# Sheet1.net
KiCad netlist of a schematic drawn in Altium Designer
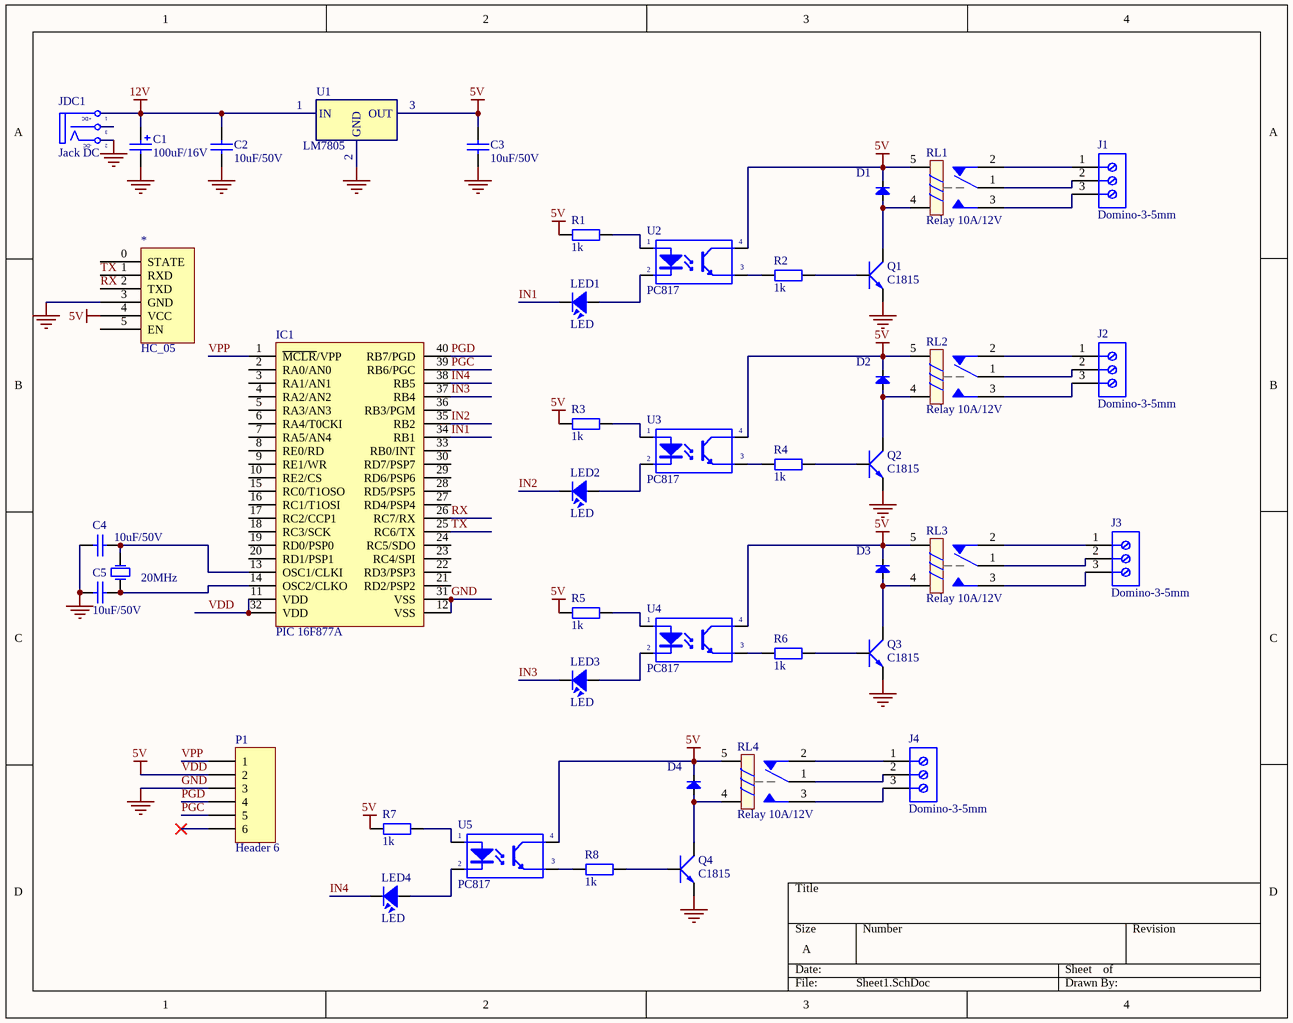
[diagram p0: Sheet1.SchDoc]

(export (version "E")
  (design (tool "Eeschema 10.0.6"))
  (components
    (comp (ref "*") (value "HC_05") (footprint "HC_05") (libsource (lib "C_20_addition") (part "HC_05")))
    (comp (ref "C1")
      (value "100uF/16V")
      (footprint "CAP-SM-AL-SIZE-D-D6L6")
      (description "CAP ALUM 100UF 20% 16V SMD")
      (fields
        (field (name "MANUFACTURER") "Nichicon")
        (field (name "MANUFACTURER PART NUMBER") "UWX1C101MCL1GB")
      )
      (libsource (lib "Capacitor") (part "Cap-Al-100uF-16V-D6L5"))
    )
    (comp (ref "C2")
      (value "10uF/50V")
      (footprint "CAP-SM-0805")
      (description "CAP CER 10UF 50V X5R 0805")
      (fields
        (field (name "MANUFACTURER") "Yageo")
        (field (name "MANUFACTURER PART NUMBER") "CC0805KKX5R9BB106")
      )
      (libsource (lib "Capacitor") (part "Cap-10uF-50V-0805"))
    )
    (comp (ref "C3")
      (value "10uF/50V")
      (footprint "CAP-SM-0805")
      (description "CAP CER 10UF 50V X5R 0805")
      (fields
        (field (name "MANUFACTURER") "Yageo")
        (field (name "MANUFACTURER PART NUMBER") "CC0805KKX5R9BB106")
      )
      (libsource (lib "Capacitor") (part "Cap-10uF-50V-0805"))
    )
    (comp (ref "C4")
      (value "10uF/50V")
      (footprint "CAP-SM-0805")
      (description "CAP CER 10UF 50V X5R 0805")
      (fields
        (field (name "MANUFACTURER") "Yageo")
        (field (name "MANUFACTURER PART NUMBER") "CC0805KKX5R9BB106")
      )
      (libsource (lib "Capacitor") (part "Cap-10uF-50V-0805"))
    )
    (comp (ref "C5")
      (value "10uF/50V")
      (footprint "CAP-SM-0805")
      (description "CAP CER 10UF 50V X5R 0805")
      (fields
        (field (name "MANUFACTURER") "Yageo")
        (field (name "MANUFACTURER PART NUMBER") "CC0805KKX5R9BB106")
      )
      (libsource (lib "Capacitor") (part "Cap-10uF-50V-0805"))
    )
    (comp (ref "D1")
      (value "Diode")
      (footprint "DIO-1A")
      (description "Default Diode")
      (fields (field (name "PUBLISHER") "Altium Limited"))
      (libsource (lib "My Library") (part "Diode"))
    )
    (comp (ref "D2")
      (value "Diode")
      (footprint "DIO-1A")
      (description "Default Diode")
      (fields (field (name "PUBLISHER") "Altium Limited"))
      (libsource (lib "My Library") (part "Diode"))
    )
    (comp (ref "D3")
      (value "Diode")
      (footprint "DIO-1A")
      (description "Default Diode")
      (fields (field (name "PUBLISHER") "Altium Limited"))
      (libsource (lib "My Library") (part "Diode"))
    )
    (comp (ref "D4")
      (value "Diode")
      (footprint "DIO-1A")
      (description "Default Diode")
      (fields (field (name "PUBLISHER") "Altium Limited"))
      (libsource (lib "My Library") (part "Diode"))
    )
    (comp (ref "IC1")
      (value "PIC 16F877A")
      (footprint "DIP40/W0.6")
      (description "8K FLASH, 368B RAM, 256B EFROM")
      (fields (field (name "COPYRIGHT BY") "VanDungEvn"))
      (libsource (lib "My Library") (part "PIC16F877-PU"))
    )
    (comp (ref "J1")
      (value "Domino-3-5mm")
      (footprint "DOMINO-3-5mm")
      (description "WR-TBL Serie 1347 Horizontal Cable Entry, Pressure Clamp, pitch 5mm, 3p")
      (fields (field (name "PART NUMBER") "691134710003") (field (name "PUBLISHER") "Wurth Elektronik"))
      (libsource (lib "Header-connector") (part "Domino-3-5mm"))
    )
    (comp (ref "J2")
      (value "Domino-3-5mm")
      (footprint "DOMINO-3-5mm")
      (description "WR-TBL Serie 1347 Horizontal Cable Entry, Pressure Clamp, pitch 5mm, 3p")
      (fields (field (name "PART NUMBER") "691134710003") (field (name "PUBLISHER") "Wurth Elektronik"))
      (libsource (lib "Header-connector") (part "Domino-3-5mm"))
    )
    (comp (ref "J3")
      (value "Domino-3-5mm")
      (footprint "DOMINO-3-5mm")
      (description "WR-TBL Serie 1347 Horizontal Cable Entry, Pressure Clamp, pitch 5mm, 3p")
      (fields (field (name "PART NUMBER") "691134710003") (field (name "PUBLISHER") "Wurth Elektronik"))
      (libsource (lib "Header-connector") (part "Domino-3-5mm"))
    )
    (comp (ref "J4")
      (value "Domino-3-5mm")
      (footprint "DOMINO-3-5mm")
      (description "WR-TBL Serie 1347 Horizontal Cable Entry, Pressure Clamp, pitch 5mm, 3p")
      (fields (field (name "PART NUMBER") "691134710003") (field (name "PUBLISHER") "Wurth Elektronik"))
      (libsource (lib "Header-connector") (part "Domino-3-5mm"))
    )
    (comp (ref "JDC1")
      (value "Jack DC")
      (footprint "JACK-DC")
      (description "Jack DC input")
      (libsource (lib "Header-connector") (part "Jack DC"))
    )
    (comp (ref "LED1")
      (value "LED")
      (footprint "LED-3")
      (description "LED Single colour Green and Red")
      (libsource (lib "syhaunguyen") (part "LED"))
    )
    (comp (ref "LED2")
      (value "LED")
      (footprint "LED-3")
      (description "LED Single colour Green and Red")
      (libsource (lib "syhaunguyen") (part "LED"))
    )
    (comp (ref "LED3")
      (value "LED")
      (footprint "LED-3")
      (description "LED Single colour Green and Red")
      (libsource (lib "syhaunguyen") (part "LED"))
    )
    (comp (ref "LED4")
      (value "LED")
      (footprint "LED-3")
      (description "LED Single colour Green and Red")
      (libsource (lib "syhaunguyen") (part "LED"))
    )
    (comp (ref "P1")
      (value "Header 6")
      (footprint "HDR1X6")
      (description "Header, 6-Pin")
      (fields (field (name "PUBLISHER") "Altium Limited"))
      (libsource (lib "My Library") (part "Header 6"))
    )
    (comp (ref "Q1")
      (value "C1815")
      (footprint "QTO-92")
      (description "NPN 600mW, ECB")
      (libsource (lib "syhaunguyen") (part "C1815"))
    )
    (comp (ref "Q2")
      (value "C1815")
      (footprint "QTO-92")
      (description "NPN 600mW, ECB")
      (libsource (lib "syhaunguyen") (part "C1815"))
    )
    (comp (ref "Q3")
      (value "C1815")
      (footprint "QTO-92")
      (description "NPN 600mW, ECB")
      (libsource (lib "syhaunguyen") (part "C1815"))
    )
    (comp (ref "Q4")
      (value "C1815")
      (footprint "QTO-92")
      (description "NPN 600mW, ECB")
      (libsource (lib "syhaunguyen") (part "C1815"))
    )
    (comp (ref "R1")
      (value "1k")
      (footprint "R1/4W")
      (description "Resistor 1/4W")
      (libsource (lib "My Library") (part "R1/4W"))
    )
    (comp (ref "R2")
      (value "1k")
      (footprint "R1/4W")
      (description "Resistor 1/4W")
      (libsource (lib "My Library") (part "R1/4W"))
    )
    (comp (ref "R3")
      (value "1k")
      (footprint "R1/4W")
      (description "Resistor 1/4W")
      (libsource (lib "My Library") (part "R1/4W"))
    )
    (comp (ref "R4")
      (value "1k")
      (footprint "R1/4W")
      (description "Resistor 1/4W")
      (libsource (lib "My Library") (part "R1/4W"))
    )
    (comp (ref "R5")
      (value "1k")
      (footprint "R1/4W")
      (description "Resistor 1/4W")
      (libsource (lib "My Library") (part "R1/4W"))
    )
    (comp (ref "R6")
      (value "1k")
      (footprint "R1/4W")
      (description "Resistor 1/4W")
      (libsource (lib "My Library") (part "R1/4W"))
    )
    (comp (ref "R7")
      (value "1k")
      (footprint "R1/4W")
      (description "Resistor 1/4W")
      (libsource (lib "My Library") (part "R1/4W"))
    )
    (comp (ref "R8")
      (value "1k")
      (footprint "R1/4W")
      (description "Resistor 1/4W")
      (libsource (lib "My Library") (part "R1/4W"))
    )
    (comp (ref "RL1")
      (value "Relay 10A/12V")
      (footprint "RL_SPDT_10A")
      (description "Relay SPDT,10A - 12VDC 5 Pin")
      (libsource (lib "My Library") (part "Relay 1"))
    )
    (comp (ref "RL2")
      (value "Relay 10A/12V")
      (footprint "RL_SPDT_10A")
      (description "Relay SPDT,10A - 12VDC 5 Pin")
      (libsource (lib "My Library") (part "Relay 1"))
    )
    (comp (ref "RL3")
      (value "Relay 10A/12V")
      (footprint "RL_SPDT_10A")
      (description "Relay SPDT,10A - 12VDC 5 Pin")
      (libsource (lib "My Library") (part "Relay 1"))
    )
    (comp (ref "RL4")
      (value "Relay 10A/12V")
      (footprint "RL_SPDT_10A")
      (description "Relay SPDT,10A - 12VDC 5 Pin")
      (libsource (lib "My Library") (part "Relay 1"))
    )
    (comp (ref "U1")
      (value "LM7805")
      (footprint "QTO-220")
      (description "Positive Voltage Regulator")
      (libsource (lib "PIF_C16_2_lib") (part "LM7805"))
    )
    (comp (ref "U2")
      (value "PC817")
      (footprint "DIP4/W0.3")
      (description "Single Opto")
      (libsource (lib "syhaunguyen") (part "PC817"))
    )
    (comp (ref "U3")
      (value "PC817")
      (footprint "DIP4/W0.3")
      (description "Single Opto")
      (libsource (lib "syhaunguyen") (part "PC817"))
    )
    (comp (ref "U4")
      (value "PC817")
      (footprint "DIP4/W0.3")
      (description "Single Opto")
      (libsource (lib "syhaunguyen") (part "PC817"))
    )
    (comp (ref "U5")
      (value "PC817")
      (footprint "DIP4/W0.3")
      (description "Single Opto")
      (libsource (lib "syhaunguyen") (part "PC817"))
    )
    (comp (ref "Y1")
      (value "20MHz")
      (footprint "XTAL")
      (description "Crystal Oscillator")
      (fields (field (name "PUBLISHER") "Altium Limited"))
      (libsource (lib "My Library") (part "XTAL"))
    )
  )
  (nets
    (net (code "1") (name "/IN1") (class "Default")
      (node (ref "IC1") (pin "34") (pinfunction "RB1_34") (pintype "passive"))
      (node (ref "LED1") (pin "2") (pinfunction "2_2") (pintype "passive"))
    )
    (net (code "2") (name "/IN2") (class "Default")
      (node (ref "IC1") (pin "35") (pinfunction "RB2_35") (pintype "passive"))
      (node (ref "LED2") (pin "2") (pinfunction "2_2") (pintype "passive"))
    )
    (net (code "3") (name "/IN3") (class "Default")
      (node (ref "IC1") (pin "37") (pinfunction "RB4_37") (pintype "passive"))
      (node (ref "LED3") (pin "2") (pinfunction "2_2") (pintype "passive"))
    )
    (net (code "4") (name "/IN4") (class "Default")
      (node (ref "IC1") (pin "38") (pinfunction "RB5_38") (pintype "passive"))
      (node (ref "LED4") (pin "2") (pinfunction "2_2") (pintype "passive"))
    )
    (net (code "5") (name "/PGC") (class "Default")
      (node (ref "IC1") (pin "39") (pinfunction "RB6/PGC_39") (pintype "passive"))
      (node (ref "P1") (pin "5") (pinfunction "5_5") (pintype "passive"))
    )
    (net (code "6") (name "/PGD") (class "Default")
      (node (ref "IC1") (pin "40") (pinfunction "RB7/PGD_40") (pintype "passive"))
      (node (ref "P1") (pin "4") (pinfunction "4_4") (pintype "passive"))
    )
    (net (code "7") (name "/RX") (class "Default")
      (node (ref "*") (pin "2") (pinfunction "TXD_2") (pintype "passive"))
      (node (ref "IC1") (pin "26") (pinfunction "RC7/RX_26") (pintype "passive"))
    )
    (net (code "8") (name "/TX") (class "Default")
      (node (ref "*") (pin "1") (pinfunction "RXD_1") (pintype "passive"))
      (node (ref "IC1") (pin "25") (pinfunction "RC6/TX_25") (pintype "passive"))
    )
    (net (code "9") (name "/VPP") (class "Default")
      (node (ref "IC1") (pin "1") (pinfunction "~{MCLR}/VPP_1") (pintype "passive"))
      (node (ref "P1") (pin "1") (pinfunction "1_1") (pintype "passive"))
    )
    (net (code "10") (name "5V") (class "Default")
      (node (ref "*") (pin "4") (pinfunction "VCC_4") (pintype "passive"))
      (node (ref "C3") (pin "2") (pinfunction "2_2") (pintype "passive"))
      (node (ref "D1") (pin "2") (pinfunction "K_2") (pintype "passive"))
      (node (ref "D2") (pin "2") (pinfunction "K_2") (pintype "passive"))
      (node (ref "D3") (pin "2") (pinfunction "K_2") (pintype "passive"))
      (node (ref "D4") (pin "2") (pinfunction "K_2") (pintype "passive"))
      (node (ref "IC1") (pin "11") (pinfunction "VDD_11") (pintype "passive"))
      (node (ref "IC1") (pin "32") (pinfunction "VDD_32") (pintype "passive"))
      (node (ref "P1") (pin "2") (pinfunction "2_2") (pintype "passive"))
      (node (ref "R1") (pin "1") (pinfunction "1_1") (pintype "passive"))
      (node (ref "R3") (pin "1") (pinfunction "1_1") (pintype "passive"))
      (node (ref "R5") (pin "1") (pinfunction "1_1") (pintype "passive"))
      (node (ref "R7") (pin "1") (pinfunction "1_1") (pintype "passive"))
      (node (ref "RL1") (pin "5") (pinfunction "5_5") (pintype "passive"))
      (node (ref "RL2") (pin "5") (pinfunction "5_5") (pintype "passive"))
      (node (ref "RL3") (pin "5") (pinfunction "5_5") (pintype "passive"))
      (node (ref "RL4") (pin "5") (pinfunction "5_5") (pintype "passive"))
      (node (ref "U1") (pin "3") (pinfunction "OUT_3") (pintype "power_in"))
      (node (ref "U2") (pin "4") (pinfunction "C_4") (pintype "passive"))
      (node (ref "U3") (pin "4") (pinfunction "C_4") (pintype "passive"))
      (node (ref "U4") (pin "4") (pinfunction "C_4") (pintype "passive"))
      (node (ref "U5") (pin "4") (pinfunction "C_4") (pintype "passive"))
    )
    (net (code "11") (name "12V") (class "Default")
      (node (ref "C1") (pin "1") (pinfunction "1_1") (pintype "passive"))
      (node (ref "C2") (pin "2") (pinfunction "2_2") (pintype "passive"))
      (node (ref "JDC1") (pin "1") (pinfunction "T_1") (pintype "passive"))
      (node (ref "U1") (pin "1") (pinfunction "IN_1") (pintype "power_in"))
    )
    (net (code "12") (name "GND") (class "Default")
      (node (ref "*") (pin "3") (pinfunction "GND_3") (pintype "passive"))
      (node (ref "C1") (pin "2") (pinfunction "2_2") (pintype "passive"))
      (node (ref "C2") (pin "1") (pinfunction "1_1") (pintype "passive"))
      (node (ref "C3") (pin "1") (pinfunction "1_1") (pintype "passive"))
      (node (ref "C4") (pin "2") (pinfunction "2_2") (pintype "passive"))
      (node (ref "C5") (pin "2") (pinfunction "2_2") (pintype "passive"))
      (node (ref "IC1") (pin "12") (pinfunction "VSS_12") (pintype "passive"))
      (node (ref "IC1") (pin "31") (pinfunction "VSS_31") (pintype "passive"))
      (node (ref "JDC1") (pin "2") (pinfunction "TN_2") (pintype "passive"))
      (node (ref "P1") (pin "3") (pinfunction "3_3") (pintype "passive"))
      (node (ref "Q1") (pin "1") (pinfunction "E_1") (pintype "passive"))
      (node (ref "Q2") (pin "1") (pinfunction "E_1") (pintype "passive"))
      (node (ref "Q3") (pin "1") (pinfunction "E_1") (pintype "passive"))
      (node (ref "Q4") (pin "1") (pinfunction "E_1") (pintype "passive"))
      (node (ref "U1") (pin "2") (pinfunction "GND_2") (pintype "power_in"))
    )
    (net (code "13") (name "Net-(D1-A)") (class "Default")
      (node (ref "D1") (pin "1") (pinfunction "A_1") (pintype "passive"))
      (node (ref "Q1") (pin "2") (pinfunction "C_2") (pintype "passive"))
      (node (ref "RL1") (pin "4") (pinfunction "4_4") (pintype "passive"))
    )
    (net (code "14") (name "Net-(D2-A)") (class "Default")
      (node (ref "D2") (pin "1") (pinfunction "A_1") (pintype "passive"))
      (node (ref "Q2") (pin "2") (pinfunction "C_2") (pintype "passive"))
      (node (ref "RL2") (pin "4") (pinfunction "4_4") (pintype "passive"))
    )
    (net (code "15") (name "Net-(D3-A)") (class "Default")
      (node (ref "D3") (pin "1") (pinfunction "A_1") (pintype "passive"))
      (node (ref "Q3") (pin "2") (pinfunction "C_2") (pintype "passive"))
      (node (ref "RL3") (pin "4") (pinfunction "4_4") (pintype "passive"))
    )
    (net (code "16") (name "Net-(D4-A)") (class "Default")
      (node (ref "D4") (pin "1") (pinfunction "A_1") (pintype "passive"))
      (node (ref "Q4") (pin "2") (pinfunction "C_2") (pintype "passive"))
      (node (ref "RL4") (pin "4") (pinfunction "4_4") (pintype "passive"))
    )
    (net (code "17") (name "Net-(IC1-OSC1{slash}CLKI)") (class "Default")
      (node (ref "C4") (pin "1") (pinfunction "1_1") (pintype "passive"))
      (node (ref "IC1") (pin "13") (pinfunction "OSC1/CLKI_13") (pintype "passive"))
      (node (ref "Y1") (pin "2") (pinfunction "OSC2_2") (pintype "passive"))
    )
    (net (code "18") (name "Net-(IC1-OSC2{slash}CLKO)") (class "Default")
      (node (ref "C5") (pin "1") (pinfunction "1_1") (pintype "passive"))
      (node (ref "IC1") (pin "14") (pinfunction "OSC2/CLKO_14") (pintype "passive"))
      (node (ref "Y1") (pin "1") (pinfunction "OSC1_1") (pintype "passive"))
    )
    (net (code "19") (name "Net-(J1-Pad1)") (class "Default")
      (node (ref "J1") (pin "1") (pinfunction "1_1") (pintype "passive"))
      (node (ref "RL1") (pin "2") (pinfunction "2_2") (pintype "passive"))
    )
    (net (code "20") (name "Net-(J1-Pad2)") (class "Default")
      (node (ref "J1") (pin "2") (pinfunction "2_2") (pintype "passive"))
      (node (ref "RL1") (pin "1") (pinfunction "1_1") (pintype "passive"))
    )
    (net (code "21") (name "Net-(J1-Pad3)") (class "Default")
      (node (ref "J1") (pin "3") (pinfunction "3_3") (pintype "passive"))
      (node (ref "RL1") (pin "3") (pinfunction "3_3") (pintype "passive"))
    )
    (net (code "22") (name "Net-(J2-Pad1)") (class "Default")
      (node (ref "J2") (pin "1") (pinfunction "1_1") (pintype "passive"))
      (node (ref "RL2") (pin "2") (pinfunction "2_2") (pintype "passive"))
    )
    (net (code "23") (name "Net-(J2-Pad2)") (class "Default")
      (node (ref "J2") (pin "2") (pinfunction "2_2") (pintype "passive"))
      (node (ref "RL2") (pin "1") (pinfunction "1_1") (pintype "passive"))
    )
    (net (code "24") (name "Net-(J2-Pad3)") (class "Default")
      (node (ref "J2") (pin "3") (pinfunction "3_3") (pintype "passive"))
      (node (ref "RL2") (pin "3") (pinfunction "3_3") (pintype "passive"))
    )
    (net (code "25") (name "Net-(J3-Pad1)") (class "Default")
      (node (ref "J3") (pin "1") (pinfunction "1_1") (pintype "passive"))
      (node (ref "RL3") (pin "2") (pinfunction "2_2") (pintype "passive"))
    )
    (net (code "26") (name "Net-(J3-Pad2)") (class "Default")
      (node (ref "J3") (pin "2") (pinfunction "2_2") (pintype "passive"))
      (node (ref "RL3") (pin "1") (pinfunction "1_1") (pintype "passive"))
    )
    (net (code "27") (name "Net-(J3-Pad3)") (class "Default")
      (node (ref "J3") (pin "3") (pinfunction "3_3") (pintype "passive"))
      (node (ref "RL3") (pin "3") (pinfunction "3_3") (pintype "passive"))
    )
    (net (code "28") (name "Net-(J4-Pad1)") (class "Default")
      (node (ref "J4") (pin "1") (pinfunction "1_1") (pintype "passive"))
      (node (ref "RL4") (pin "2") (pinfunction "2_2") (pintype "passive"))
    )
    (net (code "29") (name "Net-(J4-Pad2)") (class "Default")
      (node (ref "J4") (pin "2") (pinfunction "2_2") (pintype "passive"))
      (node (ref "RL4") (pin "1") (pinfunction "1_1") (pintype "passive"))
    )
    (net (code "30") (name "Net-(J4-Pad3)") (class "Default")
      (node (ref "J4") (pin "3") (pinfunction "3_3") (pintype "passive"))
      (node (ref "RL4") (pin "3") (pinfunction "3_3") (pintype "passive"))
    )
    (net (code "31") (name "Net-(Q1-B)") (class "Default")
      (node (ref "Q1") (pin "3") (pinfunction "B_3") (pintype "passive"))
      (node (ref "R2") (pin "2") (pinfunction "2_2") (pintype "passive"))
    )
    (net (code "32") (name "Net-(Q2-B)") (class "Default")
      (node (ref "Q2") (pin "3") (pinfunction "B_3") (pintype "passive"))
      (node (ref "R4") (pin "2") (pinfunction "2_2") (pintype "passive"))
    )
    (net (code "33") (name "Net-(Q3-B)") (class "Default")
      (node (ref "Q3") (pin "3") (pinfunction "B_3") (pintype "passive"))
      (node (ref "R6") (pin "2") (pinfunction "2_2") (pintype "passive"))
    )
    (net (code "34") (name "Net-(Q4-B)") (class "Default")
      (node (ref "Q4") (pin "3") (pinfunction "B_3") (pintype "passive"))
      (node (ref "R8") (pin "2") (pinfunction "2_2") (pintype "passive"))
    )
    (net (code "35") (name "Net-(U2-A)") (class "Default")
      (node (ref "R1") (pin "2") (pinfunction "2_2") (pintype "passive"))
      (node (ref "U2") (pin "1") (pinfunction "A_1") (pintype "passive"))
    )
    (net (code "36") (name "Net-(U2-E)") (class "Default")
      (node (ref "R2") (pin "1") (pinfunction "1_1") (pintype "passive"))
      (node (ref "U2") (pin "3") (pinfunction "E_3") (pintype "passive"))
    )
    (net (code "37") (name "Net-(U2-K)") (class "Default")
      (node (ref "LED1") (pin "1") (pinfunction "1_1") (pintype "passive"))
      (node (ref "U2") (pin "2") (pinfunction "K_2") (pintype "passive"))
    )
    (net (code "38") (name "Net-(U3-A)") (class "Default")
      (node (ref "R3") (pin "2") (pinfunction "2_2") (pintype "passive"))
      (node (ref "U3") (pin "1") (pinfunction "A_1") (pintype "passive"))
    )
    (net (code "39") (name "Net-(U3-E)") (class "Default")
      (node (ref "R4") (pin "1") (pinfunction "1_1") (pintype "passive"))
      (node (ref "U3") (pin "3") (pinfunction "E_3") (pintype "passive"))
    )
    (net (code "40") (name "Net-(U3-K)") (class "Default")
      (node (ref "LED2") (pin "1") (pinfunction "1_1") (pintype "passive"))
      (node (ref "U3") (pin "2") (pinfunction "K_2") (pintype "passive"))
    )
    (net (code "41") (name "Net-(U4-A)") (class "Default")
      (node (ref "R5") (pin "2") (pinfunction "2_2") (pintype "passive"))
      (node (ref "U4") (pin "1") (pinfunction "A_1") (pintype "passive"))
    )
    (net (code "42") (name "Net-(U4-E)") (class "Default")
      (node (ref "R6") (pin "1") (pinfunction "1_1") (pintype "passive"))
      (node (ref "U4") (pin "3") (pinfunction "E_3") (pintype "passive"))
    )
    (net (code "43") (name "Net-(U4-K)") (class "Default")
      (node (ref "LED3") (pin "1") (pinfunction "1_1") (pintype "passive"))
      (node (ref "U4") (pin "2") (pinfunction "K_2") (pintype "passive"))
    )
    (net (code "44") (name "Net-(U5-A)") (class "Default")
      (node (ref "R7") (pin "2") (pinfunction "2_2") (pintype "passive"))
      (node (ref "U5") (pin "1") (pinfunction "A_1") (pintype "passive"))
    )
    (net (code "45") (name "Net-(U5-E)") (class "Default")
      (node (ref "R8") (pin "1") (pinfunction "1_1") (pintype "passive"))
      (node (ref "U5") (pin "3") (pinfunction "E_3") (pintype "passive"))
    )
    (net (code "46") (name "Net-(U5-K)") (class "Default")
      (node (ref "LED4") (pin "1") (pinfunction "1_1") (pintype "passive"))
      (node (ref "U5") (pin "2") (pinfunction "K_2") (pintype "passive"))
    )
    (net (code "47") (name "unconnected-(*-EN-Pad5)") (class "Default")
      (node (ref "*") (pin "5") (pinfunction "EN_5") (pintype "passive"))
    )
    (net (code "48") (name "unconnected-(*-STATE-Pad0)") (class "Default")
      (node (ref "*") (pin "0") (pinfunction "STATE_0") (pintype "passive"))
    )
    (net (code "49") (name "unconnected-(IC1-RA0{slash}AN0-Pad2)") (class "Default")
      (node (ref "IC1") (pin "2") (pinfunction "RA0/AN0_2") (pintype "passive"))
    )
    (net (code "50") (name "unconnected-(IC1-RA1{slash}AN1-Pad3)") (class "Default")
      (node (ref "IC1") (pin "3") (pinfunction "RA1/AN1_3") (pintype "passive"))
    )
    (net (code "51") (name "unconnected-(IC1-RA2{slash}AN2-Pad4)") (class "Default")
      (node (ref "IC1") (pin "4") (pinfunction "RA2/AN2_4") (pintype "passive"))
    )
    (net (code "52") (name "unconnected-(IC1-RA3{slash}AN3-Pad5)") (class "Default")
      (node (ref "IC1") (pin "5") (pinfunction "RA3/AN3_5") (pintype "passive"))
    )
    (net (code "53") (name "unconnected-(IC1-RA4{slash}T0CKI-Pad6)") (class "Default")
      (node (ref "IC1") (pin "6") (pinfunction "RA4/T0CKI_6") (pintype "passive"))
    )
    (net (code "54") (name "unconnected-(IC1-RA5{slash}AN4-Pad7)") (class "Default")
      (node (ref "IC1") (pin "7") (pinfunction "RA5/AN4_7") (pintype "passive"))
    )
    (net (code "55") (name "unconnected-(IC1-RB0{slash}INT-Pad33)") (class "Default")
      (node (ref "IC1") (pin "33") (pinfunction "RB0/INT_33") (pintype "passive"))
    )
    (net (code "56") (name "unconnected-(IC1-RB3{slash}PGM-Pad36)") (class "Default")
      (node (ref "IC1") (pin "36") (pinfunction "RB3/PGM_36") (pintype "passive"))
    )
    (net (code "57") (name "unconnected-(IC1-RC0{slash}T1OSO-Pad15)") (class "Default")
      (node (ref "IC1") (pin "15") (pinfunction "RC0/T1OSO_15") (pintype "passive"))
    )
    (net (code "58") (name "unconnected-(IC1-RC1{slash}T1OSI-Pad16)") (class "Default")
      (node (ref "IC1") (pin "16") (pinfunction "RC1/T1OSI_16") (pintype "passive"))
    )
    (net (code "59") (name "unconnected-(IC1-RC2{slash}CCP1-Pad17)") (class "Default")
      (node (ref "IC1") (pin "17") (pinfunction "RC2/CCP1_17") (pintype "passive"))
    )
    (net (code "60") (name "unconnected-(IC1-RC3{slash}SCK-Pad18)") (class "Default")
      (node (ref "IC1") (pin "18") (pinfunction "RC3/SCK_18") (pintype "passive"))
    )
    (net (code "61") (name "unconnected-(IC1-RC4{slash}SPI-Pad23)") (class "Default")
      (node (ref "IC1") (pin "23") (pinfunction "RC4/SPI_23") (pintype "passive"))
    )
    (net (code "62") (name "unconnected-(IC1-RC5{slash}SDO-Pad24)") (class "Default")
      (node (ref "IC1") (pin "24") (pinfunction "RC5/SDO_24") (pintype "passive"))
    )
    (net (code "63") (name "unconnected-(IC1-RD0{slash}PSP0-Pad19)") (class "Default")
      (node (ref "IC1") (pin "19") (pinfunction "RD0/PSP0_19") (pintype "passive"))
    )
    (net (code "64") (name "unconnected-(IC1-RD1{slash}PSP1-Pad20)") (class "Default")
      (node (ref "IC1") (pin "20") (pinfunction "RD1/PSP1_20") (pintype "passive"))
    )
    (net (code "65") (name "unconnected-(IC1-RD2{slash}PSP2-Pad21)") (class "Default")
      (node (ref "IC1") (pin "21") (pinfunction "RD2/PSP2_21") (pintype "passive"))
    )
    (net (code "66") (name "unconnected-(IC1-RD3{slash}PSP3-Pad22)") (class "Default")
      (node (ref "IC1") (pin "22") (pinfunction "RD3/PSP3_22") (pintype "passive"))
    )
    (net (code "67") (name "unconnected-(IC1-RD4{slash}PSP4-Pad27)") (class "Default")
      (node (ref "IC1") (pin "27") (pinfunction "RD4/PSP4_27") (pintype "passive"))
    )
    (net (code "68") (name "unconnected-(IC1-RD5{slash}PSP5-Pad28)") (class "Default")
      (node (ref "IC1") (pin "28") (pinfunction "RD5/PSP5_28") (pintype "passive"))
    )
    (net (code "69") (name "unconnected-(IC1-RD6{slash}PSP6-Pad29)") (class "Default")
      (node (ref "IC1") (pin "29") (pinfunction "RD6/PSP6_29") (pintype "passive"))
    )
    (net (code "70") (name "unconnected-(IC1-RD7{slash}PSP7-Pad30)") (class "Default")
      (node (ref "IC1") (pin "30") (pinfunction "RD7/PSP7_30") (pintype "passive"))
    )
    (net (code "71") (name "unconnected-(IC1-RE0{slash}RD-Pad8)") (class "Default")
      (node (ref "IC1") (pin "8") (pinfunction "RE0/RD_8") (pintype "passive"))
    )
    (net (code "72") (name "unconnected-(IC1-RE1{slash}WR-Pad9)") (class "Default")
      (node (ref "IC1") (pin "9") (pinfunction "RE1/WR_9") (pintype "passive"))
    )
    (net (code "73") (name "unconnected-(IC1-RE2{slash}CS-Pad10)") (class "Default")
      (node (ref "IC1") (pin "10") (pinfunction "RE2/CS_10") (pintype "passive"))
    )
    (net (code "74") (name "unconnected-(JDC1-S-Pad3)") (class "Default")
      (node (ref "JDC1") (pin "3") (pinfunction "S_3") (pintype "power_in"))
    )
    (net (code "75") (name "unconnected-(P1-Pad6)") (class "Default")
      (node (ref "P1") (pin "6") (pinfunction "6_6") (pintype "passive+no_connect"))
    )
  )
)
